# Half_Bridge_Push_Pull_Circuit.net
KiCad netlist of a schematic drawn in Altium Designer
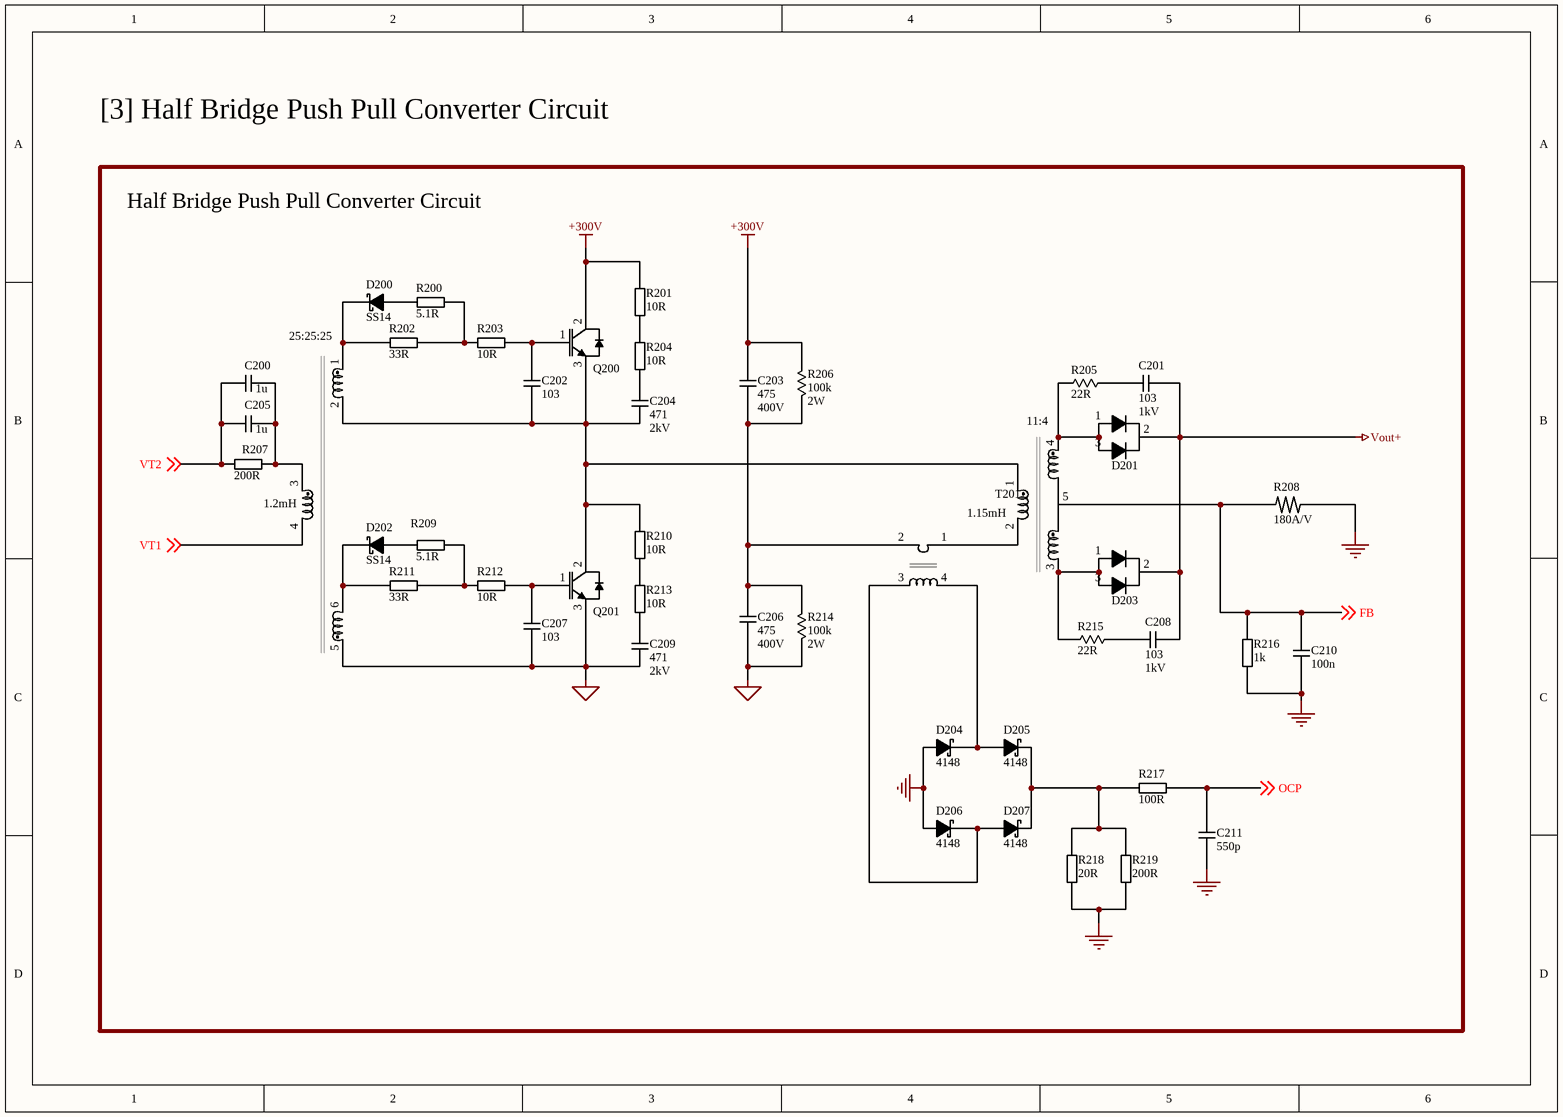
[diagram p0: Half_Bridge_Push_Pull_Circuit.SchDoc]

(export (version "E")
  (design (tool "Eeschema 10.0.6"))
  (components
    (comp (ref "C200")
      (value "1u")
      (footprint "Cap_SMD_0805")
      (description "SMD Ceramic Capacitor")
      (libsource (lib "LamThach_Sch_Lib") (part "Cap_SMD_Ceramic"))
    )
    (comp (ref "C201")
      (value "103")
      (footprint "Cap_THD_HVCeramic_5mm")
      (description "THD Ceramic Capacitor")
      (fields (field (name "VOLTAGE") "1kV"))
      (libsource (lib "LamThach_Sch_Lib") (part "Cap_THD_Ceramic"))
    )
    (comp (ref "C202")
      (value "103")
      (footprint "Cap_THD_Ceramic_5mm")
      (description "THD Ceramic Capacitor")
      (fields (field (name "VOLTAGE") "V"))
      (libsource (lib "LamThach_Sch_Lib") (part "Cap_THD_Ceramic"))
    )
    (comp (ref "C203")
      (value "475")
      (footprint "Cap_THD_Film_22.5mm")
      (description "THD Film Capacitor")
      (fields (field (name "VOLTAGE") "400V"))
      (libsource (lib "LamThach_Sch_Lib") (part "Cap_THD_Film"))
    )
    (comp (ref "C204")
      (value "471")
      (footprint "Cap_THD_HVCeramic_5mm")
      (description "THD Ceramic Capacitor")
      (fields (field (name "VOLTAGE") "2kV"))
      (libsource (lib "LamThach_Sch_Lib") (part "Cap_THD_Ceramic"))
    )
    (comp (ref "C205")
      (value "1u")
      (footprint "Cap_SMD_0805")
      (description "SMD Ceramic Capacitor")
      (libsource (lib "LamThach_Sch_Lib") (part "Cap_SMD_Ceramic"))
    )
    (comp (ref "C206")
      (value "475")
      (footprint "Cap_THD_Film_22.5mm")
      (description "THD Film Capacitor")
      (fields (field (name "VOLTAGE") "400V"))
      (libsource (lib "LamThach_Sch_Lib") (part "Cap_THD_Film"))
    )
    (comp (ref "C207")
      (value "103")
      (footprint "Cap_THD_Ceramic_5mm")
      (description "THD Ceramic Capacitor")
      (fields (field (name "VOLTAGE") "V"))
      (libsource (lib "LamThach_Sch_Lib") (part "Cap_THD_Ceramic"))
    )
    (comp (ref "C208")
      (value "103")
      (footprint "Cap_THD_HVCeramic_5mm")
      (description "THD Ceramic Capacitor")
      (fields (field (name "VOLTAGE") "1kV"))
      (libsource (lib "LamThach_Sch_Lib") (part "Cap_THD_Ceramic"))
    )
    (comp (ref "C209")
      (value "471")
      (footprint "Cap_THD_HVCeramic_5mm")
      (description "THD Ceramic Capacitor")
      (fields (field (name "VOLTAGE") "2kV"))
      (libsource (lib "LamThach_Sch_Lib") (part "Cap_THD_Ceramic"))
    )
    (comp (ref "C210")
      (value "100n")
      (footprint "Cap_SMD_0805")
      (description "0805 SMD Capacitor")
      (libsource (lib "LamThach_Sch_Lib") (part "Cap_SMD_0805"))
    )
    (comp (ref "C211")
      (value "550p")
      (footprint "Cap_SMD_0805")
      (description "0805 SMD Capacitor")
      (libsource (lib "LamThach_Sch_Lib") (part "Cap_SMD_0805"))
    )
    (comp (ref "D200")
      (value "SS14")
      (footprint "Diode_SMD_4.3mm")
      (description "Schottky Diode")
      (libsource (lib "LamThach_Sch_Lib") (part "Diode_Schottky"))
    )
    (comp (ref "D201")
      (value "STTH6003")
      (footprint "TO247 - 5.46mm")
      (description "Diode Ultra Fast Recovery Rectifier 300V 60A 3-Pin (3+Tab) TO-247 Tube")
      (fields
        (field (name "MANUFACTURER") "STMicroelectronics")
        (field (name "MANUFACTURER PART NUMBER") "STTH6003CW")
      )
      (libsource (lib "LamThach_Sch_Lib") (part "Diode_STTH6003"))
    )
    (comp (ref "D202")
      (value "SS14")
      (footprint "Diode_SMD_4.3mm")
      (description "Schottky Diode")
      (libsource (lib "LamThach_Sch_Lib") (part "Diode_Schottky"))
    )
    (comp (ref "D203")
      (value "STTH6003")
      (footprint "TO247 - 5.46mm")
      (description "Diode Ultra Fast Recovery Rectifier 300V 60A 3-Pin (3+Tab) TO-247 Tube")
      (fields
        (field (name "MANUFACTURER") "STMicroelectronics")
        (field (name "MANUFACTURER PART NUMBER") "STTH6003CW")
      )
      (libsource (lib "LamThach_Sch_Lib") (part "Diode_STTH6003"))
    )
    (comp (ref "D204")
      (value "4148")
      (footprint "Diode_SMD_4.8mm")
      (description "Rectifier Diode Small Signal Switching 100V 0.2A 4ns Automotive 2-Pin DO-35 Ammo")
      (fields
        (field (name "MANUFACTURER") "NXP Semiconductors")
        (field (name "MANUFACTURER PART NUMBER") "1N4148")
      )
      (libsource (lib "LamThach_Sch_Lib") (part "Diode_1N4148"))
    )
    (comp (ref "D205")
      (value "4148")
      (footprint "Diode_SMD_4.8mm")
      (description "Rectifier Diode Small Signal Switching 100V 0.2A 4ns Automotive 2-Pin DO-35 Ammo")
      (fields
        (field (name "MANUFACTURER") "NXP Semiconductors")
        (field (name "MANUFACTURER PART NUMBER") "1N4148")
      )
      (libsource (lib "LamThach_Sch_Lib") (part "Diode_1N4148"))
    )
    (comp (ref "D206")
      (value "4148")
      (footprint "Diode_SMD_4.8mm")
      (description "Rectifier Diode Small Signal Switching 100V 0.2A 4ns Automotive 2-Pin DO-35 Ammo")
      (fields
        (field (name "MANUFACTURER") "NXP Semiconductors")
        (field (name "MANUFACTURER PART NUMBER") "1N4148")
      )
      (libsource (lib "LamThach_Sch_Lib") (part "Diode_1N4148"))
    )
    (comp (ref "D207")
      (value "4148")
      (footprint "Diode_SMD_4.8mm")
      (description "Rectifier Diode Small Signal Switching 100V 0.2A 4ns Automotive 2-Pin DO-35 Ammo")
      (fields
        (field (name "MANUFACTURER") "NXP Semiconductors")
        (field (name "MANUFACTURER PART NUMBER") "1N4148")
      )
      (libsource (lib "LamThach_Sch_Lib") (part "Diode_1N4148"))
    )
    (comp (ref "Q200")
      (value "IGBT_RJH60F5")
      (footprint "TO247 - 5.46mm")
      (description "Trans IGBT Chip N-CH 600V 80A 260400mW 3-Pin(3+Tab) TO-247A")
      (fields
        (field (name "MANUFACTURER") "Renesas")
        (field (name "MANUFACTURER PART NUMBER") "RJH60F5DPQ-A0#T0")
      )
      (libsource (lib "LamThach_Sch_Lib") (part "IGBT_RJH60F5"))
    )
    (comp (ref "Q201")
      (value "IGBT_RJH60F5")
      (footprint "TO247 - 5.46mm")
      (description "Trans IGBT Chip N-CH 600V 80A 260400mW 3-Pin(3+Tab) TO-247A")
      (fields
        (field (name "MANUFACTURER") "Renesas")
        (field (name "MANUFACTURER PART NUMBER") "RJH60F5DPQ-A0#T0")
      )
      (libsource (lib "LamThach_Sch_Lib") (part "IGBT_RJH60F5"))
    )
    (comp (ref "R200")
      (value "5.1R")
      (footprint "Res_SMD_1206")
      (description "SMD Resistor")
      (libsource (lib "LamThach_Sch_Lib") (part "Res_SMD"))
    )
    (comp (ref "R201")
      (value "10R")
      (footprint "Res_SMD_2512")
      (description "SMD Resistor")
      (libsource (lib "LamThach_Sch_Lib") (part "Res_SMD"))
    )
    (comp (ref "R202")
      (value "33R")
      (footprint "Res_SMD_1206")
      (description "SMD Resistor")
      (libsource (lib "LamThach_Sch_Lib") (part "Res_SMD"))
    )
    (comp (ref "R203")
      (value "10R")
      (footprint "Res_SMD_1206")
      (description "SMD Resistor")
      (libsource (lib "LamThach_Sch_Lib") (part "Res_SMD"))
    )
    (comp (ref "R204")
      (value "10R")
      (footprint "Res_SMD_2512")
      (description "SMD Resistor")
      (libsource (lib "LamThach_Sch_Lib") (part "Res_SMD"))
    )
    (comp (ref "R205")
      (value "22R")
      (footprint "Res_THD_2W_17.6mm")
      (description "THD Resistor")
      (fields (field (name "POWER") "W"))
      (libsource (lib "LamThach_Sch_Lib") (part "Res_THD"))
    )
    (comp (ref "R206")
      (value "100k")
      (footprint "Res_THD_2W_17.6mm")
      (description "THD Resistor")
      (fields (field (name "POWER") "2W"))
      (libsource (lib "LamThach_Sch_Lib") (part "Res_THD"))
    )
    (comp (ref "R207")
      (value "200R")
      (footprint "Res_SMD_1206")
      (description "SMD Resistor")
      (libsource (lib "LamThach_Sch_Lib") (part "Res_SMD"))
    )
    (comp (ref "R208")
      (value "180A/V")
      (footprint "Res_Shunt")
      (description "Shunt Resistor")
      (fields (field (name "POWER") "W"))
      (libsource (lib "LamThach_Sch_Lib") (part "Res_Shunt"))
    )
    (comp (ref "R209")
      (value "5.1R")
      (footprint "Res_SMD_1206")
      (description "SMD Resistor")
      (libsource (lib "LamThach_Sch_Lib") (part "Res_SMD"))
    )
    (comp (ref "R210")
      (value "10R")
      (footprint "Res_SMD_2512")
      (description "SMD Resistor")
      (libsource (lib "LamThach_Sch_Lib") (part "Res_SMD"))
    )
    (comp (ref "R211")
      (value "33R")
      (footprint "Res_SMD_1206")
      (description "SMD Resistor")
      (libsource (lib "LamThach_Sch_Lib") (part "Res_SMD"))
    )
    (comp (ref "R212")
      (value "10R")
      (footprint "Res_SMD_1206")
      (description "SMD Resistor")
      (libsource (lib "LamThach_Sch_Lib") (part "Res_SMD"))
    )
    (comp (ref "R213")
      (value "10R")
      (footprint "Res_SMD_2512")
      (description "SMD Resistor")
      (libsource (lib "LamThach_Sch_Lib") (part "Res_SMD"))
    )
    (comp (ref "R214")
      (value "100k")
      (footprint "Res_THD_2W_17.6mm")
      (description "THD Resistor")
      (fields (field (name "POWER") "2W"))
      (libsource (lib "LamThach_Sch_Lib") (part "Res_THD"))
    )
    (comp (ref "R215")
      (value "22R")
      (footprint "Res_THD_2W_17.6mm")
      (description "THD Resistor")
      (fields (field (name "POWER") "W"))
      (libsource (lib "LamThach_Sch_Lib") (part "Res_THD"))
    )
    (comp (ref "R216")
      (value "1k")
      (footprint "Res_SMD_0805")
      (description "0805 SMD Resistor")
      (libsource (lib "LamThach_Sch_Lib") (part "Res_SMD_0805"))
    )
    (comp (ref "R217")
      (value "100R")
      (footprint "Res_SMD_0805")
      (description "SMD Resistor")
      (libsource (lib "LamThach_Sch_Lib") (part "Res_SMD"))
    )
    (comp (ref "R218")
      (value "20R")
      (footprint "Res_SMD_2512")
      (description "SMD Resistor")
      (libsource (lib "LamThach_Sch_Lib") (part "Res_SMD"))
    )
    (comp (ref "R219")
      (value "200R")
      (footprint "Res_SMD_2512")
      (description "SMD Resistor")
      (libsource (lib "LamThach_Sch_Lib") (part "Res_SMD"))
    )
    (comp (ref "T200")
      (value "1.2mH")
      (footprint "XFMR_BR22EEL_1178A")
      (description "25:25:25 Pulse Transformer")
      (fields (field (name "TURNS RATIO") "25:25:25"))
      (libsource (lib "LamThach_Sch_Lib") (part "XFMR_BR22EEL_1178A"))
    )
    (comp (ref "T201")
      (value "1.15mH")
      (footprint "XFMR_T56")
      (description "11:4 JiTaiXin Pulse Transformer")
      (fields (field (name "TURNS RATIO") "11:4"))
      (libsource (lib "LamThach_Sch_Lib") (part "XFMR_T56"))
    )
    (comp (ref "T202")
      (value "XFMR_E25")
      (footprint "XFMR_E25")
      (description "200:1 Current Transformer")
      (libsource (lib "LamThach_Sch_Lib") (part "XFMR_E25"))
    )
  )
  (nets
    (net (code "1") (name "+300V") (class "Default")
      (node (ref "C203") (pin "2") (pinfunction "2_2") (pintype "passive"))
      (node (ref "Q200") (pin "2") (pinfunction "C_2") (pintype "passive"))
      (node (ref "R201") (pin "2") (pinfunction "2_2") (pintype "passive"))
      (node (ref "R206") (pin "2") (pinfunction "2_2") (pintype "passive"))
    )
    (net (code "2") (name "FB") (class "Default")
      (node (ref "C210") (pin "1") (pinfunction "1_1") (pintype "passive"))
      (node (ref "R208") (pin "1") (pinfunction "1_1") (pintype "passive"))
      (node (ref "R216") (pin "1") (pinfunction "1_1") (pintype "passive"))
      (node (ref "T201") (pin "5") (pinfunction "5_5") (pintype "passive"))
    )
    (net (code "3") (name "GND") (class "Default")
      (node (ref "C210") (pin "2") (pinfunction "2_2") (pintype "passive"))
      (node (ref "C211") (pin "2") (pinfunction "2_2") (pintype "passive"))
      (node (ref "D204") (pin "1") (pinfunction "A_1") (pintype "passive"))
      (node (ref "D206") (pin "1") (pinfunction "A_1") (pintype "passive"))
      (node (ref "R208") (pin "2") (pinfunction "2_2") (pintype "passive"))
      (node (ref "R216") (pin "2") (pinfunction "2_2") (pintype "passive"))
      (node (ref "R218") (pin "2") (pinfunction "2_2") (pintype "passive"))
      (node (ref "R219") (pin "2") (pinfunction "2_2") (pintype "passive"))
    )
    (net (code "4") (name "GND_1") (class "Default")
      (node (ref "C206") (pin "1") (pinfunction "1_1") (pintype "passive"))
      (node (ref "C207") (pin "1") (pinfunction "1_1") (pintype "passive"))
      (node (ref "C209") (pin "1") (pinfunction "1_1") (pintype "passive"))
      (node (ref "Q201") (pin "3") (pinfunction "E_3") (pintype "passive"))
      (node (ref "R214") (pin "1") (pinfunction "1_1") (pintype "passive"))
      (node (ref "T200") (pin "5") (pinfunction "5_5") (pintype "passive"))
    )
    (net (code "5") (name "Net-(C200-Pad2)") (class "Default")
      (node (ref "C200") (pin "2") (pinfunction "2_2") (pintype "passive"))
      (node (ref "C205") (pin "2") (pinfunction "2_2") (pintype "passive"))
      (node (ref "R207") (pin "2") (pinfunction "2_2") (pintype "passive"))
      (node (ref "T200") (pin "3") (pinfunction "3_3") (pintype "passive"))
    )
    (net (code "6") (name "Net-(C201-Pad1)") (class "Default")
      (node (ref "C201") (pin "1") (pinfunction "1_1") (pintype "passive"))
      (node (ref "R205") (pin "2") (pinfunction "2_2") (pintype "passive"))
    )
    (net (code "7") (name "Net-(C203-Pad1)") (class "Default")
      (node (ref "C203") (pin "1") (pinfunction "1_1") (pintype "passive"))
      (node (ref "C206") (pin "2") (pinfunction "2_2") (pintype "passive"))
      (node (ref "R206") (pin "1") (pinfunction "1_1") (pintype "passive"))
      (node (ref "R214") (pin "2") (pinfunction "2_2") (pintype "passive"))
      (node (ref "T202") (pin "2") (pinfunction "2_2") (pintype "passive"))
    )
    (net (code "8") (name "Net-(C204-Pad2)") (class "Default")
      (node (ref "C204") (pin "2") (pinfunction "2_2") (pintype "passive"))
      (node (ref "R204") (pin "1") (pinfunction "1_1") (pintype "passive"))
    )
    (net (code "9") (name "Net-(C208-Pad1)") (class "Default")
      (node (ref "C208") (pin "1") (pinfunction "1_1") (pintype "passive"))
      (node (ref "R215") (pin "2") (pinfunction "2_2") (pintype "passive"))
    )
    (net (code "10") (name "Net-(C209-Pad2)") (class "Default")
      (node (ref "C209") (pin "2") (pinfunction "2_2") (pintype "passive"))
      (node (ref "R213") (pin "1") (pinfunction "1_1") (pintype "passive"))
    )
    (net (code "11") (name "Net-(D200-A)") (class "Default")
      (node (ref "D200") (pin "1") (pinfunction "A_1") (pintype "passive"))
      (node (ref "R200") (pin "1") (pinfunction "1_1") (pintype "passive"))
    )
    (net (code "12") (name "Net-(D200-K)") (class "Default")
      (node (ref "D200") (pin "2") (pinfunction "K_2") (pintype "passive"))
      (node (ref "R202") (pin "1") (pinfunction "1_1") (pintype "passive"))
      (node (ref "T200") (pin "1") (pinfunction "1_1") (pintype "passive"))
    )
    (net (code "13") (name "Net-(D201-A1)") (class "Default")
      (node (ref "D201") (pin "1") (pinfunction "A1_1") (pintype "passive"))
      (node (ref "D201") (pin "3") (pinfunction "A2_3") (pintype "passive"))
      (node (ref "R205") (pin "1") (pinfunction "1_1") (pintype "passive"))
      (node (ref "T201") (pin "4") (pinfunction "4_4") (pintype "passive"))
    )
    (net (code "14") (name "Net-(D202-A)") (class "Default")
      (node (ref "D202") (pin "1") (pinfunction "A_1") (pintype "passive"))
      (node (ref "R209") (pin "1") (pinfunction "1_1") (pintype "passive"))
    )
    (net (code "15") (name "Net-(D202-K)") (class "Default")
      (node (ref "D202") (pin "2") (pinfunction "K_2") (pintype "passive"))
      (node (ref "R211") (pin "1") (pinfunction "1_1") (pintype "passive"))
      (node (ref "T200") (pin "6") (pinfunction "6_6") (pintype "passive"))
    )
    (net (code "16") (name "Net-(D203-A1)") (class "Default")
      (node (ref "D203") (pin "1") (pinfunction "A1_1") (pintype "passive"))
      (node (ref "D203") (pin "3") (pinfunction "A2_3") (pintype "passive"))
      (node (ref "R215") (pin "1") (pinfunction "1_1") (pintype "passive"))
      (node (ref "T201") (pin "3") (pinfunction "3_3") (pintype "passive"))
    )
    (net (code "17") (name "Net-(D204-K)") (class "Default")
      (node (ref "D204") (pin "2") (pinfunction "K_2") (pintype "passive"))
      (node (ref "D205") (pin "1") (pinfunction "A_1") (pintype "passive"))
      (node (ref "T202") (pin "4") (pinfunction "4_4") (pintype "passive"))
    )
    (net (code "18") (name "Net-(D205-K)") (class "Default")
      (node (ref "D205") (pin "2") (pinfunction "K_2") (pintype "passive"))
      (node (ref "D207") (pin "2") (pinfunction "K_2") (pintype "passive"))
      (node (ref "R217") (pin "1") (pinfunction "1_1") (pintype "passive"))
      (node (ref "R218") (pin "1") (pinfunction "1_1") (pintype "passive"))
      (node (ref "R219") (pin "1") (pinfunction "1_1") (pintype "passive"))
    )
    (net (code "19") (name "Net-(D206-K)") (class "Default")
      (node (ref "D206") (pin "2") (pinfunction "K_2") (pintype "passive"))
      (node (ref "D207") (pin "1") (pinfunction "A_1") (pintype "passive"))
      (node (ref "T202") (pin "3") (pinfunction "3_3") (pintype "passive"))
    )
    (net (code "20") (name "Net-(Q200-E)") (class "Default")
      (node (ref "C202") (pin "1") (pinfunction "1_1") (pintype "passive"))
      (node (ref "C204") (pin "1") (pinfunction "1_1") (pintype "passive"))
      (node (ref "Q200") (pin "3") (pinfunction "E_3") (pintype "passive"))
      (node (ref "Q201") (pin "2") (pinfunction "C_2") (pintype "passive"))
      (node (ref "R210") (pin "2") (pinfunction "2_2") (pintype "passive"))
      (node (ref "T200") (pin "2") (pinfunction "2_2") (pintype "passive"))
      (node (ref "T201") (pin "1") (pinfunction "1_1") (pintype "passive"))
    )
    (net (code "21") (name "Net-(Q200-G)") (class "Default")
      (node (ref "C202") (pin "2") (pinfunction "2_2") (pintype "passive"))
      (node (ref "Q200") (pin "1") (pinfunction "G_1") (pintype "passive"))
      (node (ref "R203") (pin "2") (pinfunction "2_2") (pintype "passive"))
    )
    (net (code "22") (name "Net-(Q201-G)") (class "Default")
      (node (ref "C207") (pin "2") (pinfunction "2_2") (pintype "passive"))
      (node (ref "Q201") (pin "1") (pinfunction "G_1") (pintype "passive"))
      (node (ref "R212") (pin "2") (pinfunction "2_2") (pintype "passive"))
    )
    (net (code "23") (name "Net-(R200-Pad2)") (class "Default")
      (node (ref "R200") (pin "2") (pinfunction "2_2") (pintype "passive"))
      (node (ref "R202") (pin "2") (pinfunction "2_2") (pintype "passive"))
      (node (ref "R203") (pin "1") (pinfunction "1_1") (pintype "passive"))
    )
    (net (code "24") (name "Net-(R201-Pad1)") (class "Default")
      (node (ref "R201") (pin "1") (pinfunction "1_1") (pintype "passive"))
      (node (ref "R204") (pin "2") (pinfunction "2_2") (pintype "passive"))
    )
    (net (code "25") (name "Net-(R209-Pad2)") (class "Default")
      (node (ref "R209") (pin "2") (pinfunction "2_2") (pintype "passive"))
      (node (ref "R211") (pin "2") (pinfunction "2_2") (pintype "passive"))
      (node (ref "R212") (pin "1") (pinfunction "1_1") (pintype "passive"))
    )
    (net (code "26") (name "Net-(R210-Pad1)") (class "Default")
      (node (ref "R210") (pin "1") (pinfunction "1_1") (pintype "passive"))
      (node (ref "R213") (pin "2") (pinfunction "2_2") (pintype "passive"))
    )
    (net (code "27") (name "Net-(T201-Pad2)") (class "Default")
      (node (ref "T201") (pin "2") (pinfunction "2_2") (pintype "passive"))
      (node (ref "T202") (pin "1") (pinfunction "1_1") (pintype "passive"))
    )
    (net (code "28") (name "OCP") (class "Default")
      (node (ref "C211") (pin "1") (pinfunction "1_1") (pintype "passive"))
      (node (ref "R217") (pin "2") (pinfunction "2_2") (pintype "passive"))
    )
    (net (code "29") (name "VT1") (class "Default")
      (node (ref "T200") (pin "4") (pinfunction "4_4") (pintype "passive"))
    )
    (net (code "30") (name "VT2") (class "Default")
      (node (ref "C200") (pin "1") (pinfunction "1_1") (pintype "passive"))
      (node (ref "C205") (pin "1") (pinfunction "1_1") (pintype "passive"))
      (node (ref "R207") (pin "1") (pinfunction "1_1") (pintype "passive"))
    )
    (net (code "31") (name "Vout+") (class "Default")
      (node (ref "C201") (pin "2") (pinfunction "2_2") (pintype "passive"))
      (node (ref "C208") (pin "2") (pinfunction "2_2") (pintype "passive"))
      (node (ref "D201") (pin "2") (pinfunction "K_2") (pintype "passive"))
      (node (ref "D203") (pin "2") (pinfunction "K_2") (pintype "passive"))
    )
  )
)
